# cataclysm-BOTTOM.net
KiCad netlist of a schematic drawn in EAGLE
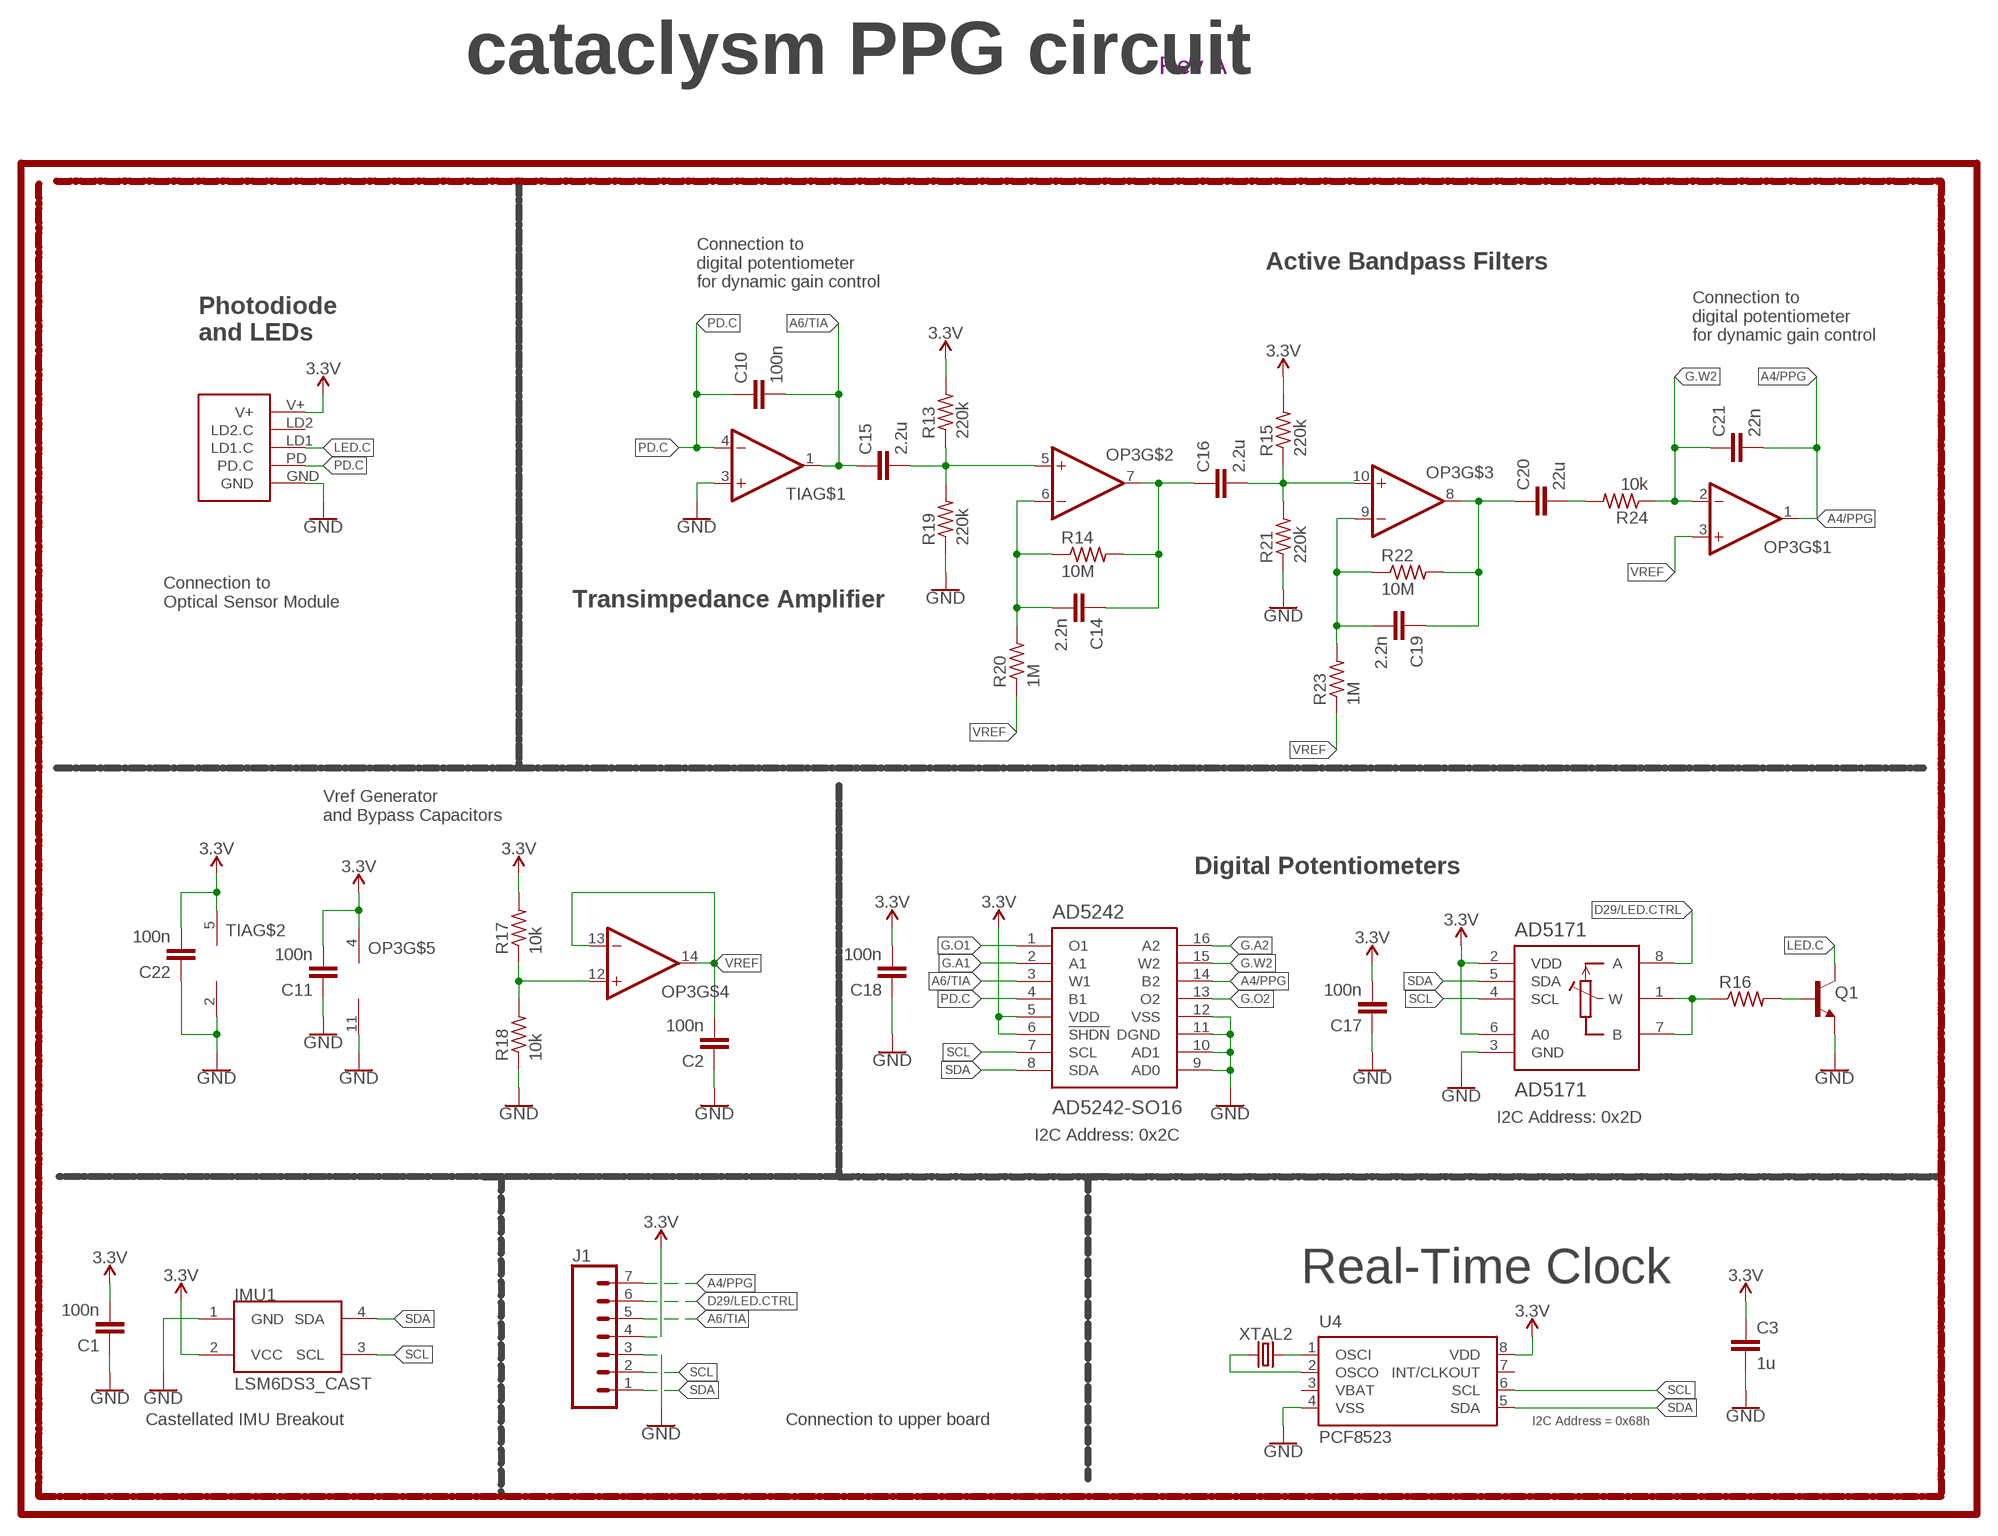
[diagram p0: schematic, sheet 1]

(export (version "E")
  (design (tool "Eeschema 10.0.6"))
  (components
    (comp (ref "AD5171")
      (value "AD5171")
      (footprint "eagle-import:SOT-23-8")
      (libsource (lib "eagle-import") (part "AD5171"))
    )
    (comp (ref "AD5242")
      (value "AD5242-SO16")
      (footprint "eagle-import:SO16")
      (libsource (lib "eagle-import") (part "AD5242-SO16"))
    )
    (comp (ref "C1")
      (value "100n")
      (footprint "eagle-import:C0603")
      (libsource (lib "eagle-import") (part "CAPACITOR0603"))
    )
    (comp (ref "C2")
      (value "100n")
      (footprint "eagle-import:C0603")
      (libsource (lib "eagle-import") (part "CAPACITOR0603"))
    )
    (comp (ref "C3")
      (value "1u")
      (footprint "eagle-import:C0603")
      (libsource (lib "eagle-import") (part "CAPACITOR0603"))
    )
    (comp (ref "C10")
      (value "100n")
      (footprint "eagle-import:C0603")
      (libsource (lib "eagle-import") (part "CAPACITOR0603"))
    )
    (comp (ref "C11")
      (value "100n")
      (footprint "eagle-import:C0603")
      (libsource (lib "eagle-import") (part "CAPACITOR0603"))
    )
    (comp (ref "C14")
      (value "2.2n")
      (footprint "eagle-import:C0603")
      (libsource (lib "eagle-import") (part "CAPACITOR0603"))
    )
    (comp (ref "C15")
      (value "2.2u")
      (footprint "eagle-import:C0603")
      (libsource (lib "eagle-import") (part "CAPACITOR0603"))
    )
    (comp (ref "C16")
      (value "2.2u")
      (footprint "eagle-import:C0603")
      (libsource (lib "eagle-import") (part "CAPACITOR0603"))
    )
    (comp (ref "C17")
      (value "100n")
      (footprint "eagle-import:C0603")
      (libsource (lib "eagle-import") (part "CAPACITOR0603"))
    )
    (comp (ref "C18")
      (value "100n")
      (footprint "eagle-import:C0603")
      (libsource (lib "eagle-import") (part "CAPACITOR0603"))
    )
    (comp (ref "C19")
      (value "2.2n")
      (footprint "eagle-import:C0603")
      (libsource (lib "eagle-import") (part "CAPACITOR0603"))
    )
    (comp (ref "C20")
      (value "22u")
      (footprint "eagle-import:C0603")
      (libsource (lib "eagle-import") (part "CAPACITOR0603"))
    )
    (comp (ref "C21")
      (value "22n")
      (footprint "eagle-import:C0603")
      (libsource (lib "eagle-import") (part "CAPACITOR0603"))
    )
    (comp (ref "C22")
      (value "100n")
      (footprint "eagle-import:C0603")
      (libsource (lib "eagle-import") (part "CAPACITOR0603"))
    )
    (comp (ref "IMU1")
      (value "LSM6DS3_CAST")
      (footprint "eagle-import:LSM6DS3_CAST")
      (libsource (lib "eagle-import") (part "LSM6DS3_CAST"))
    )
    (comp (ref "J1")
      (value "CONN_07-1.27MM")
      (footprint "eagle-import:1X07_1.27MM")
      (libsource (lib "eagle-import") (part "CONN_07-1.27MM"))
    )
    (comp (ref "LOGO1")
      (value "REVISION.A")
      (footprint "eagle-import:REV.A")
      (libsource (lib "eagle-import") (part "REVISION.A"))
    )
    (comp (ref "OP3")
      (value "OP-QUAD-SO14")
      (footprint "eagle-import:SO14")
      (libsource (lib "eagle-import") (part "OP-QUAD-SO14"))
    )
    (comp (ref "Q1")
      (value "NPN-GENERIC")
      (footprint "eagle-import:SOT23-3")
      (libsource (lib "eagle-import") (part "NPN-GENERIC"))
    )
    (comp (ref "R13")
      (value "220k")
      (footprint "eagle-import:R0603")
      (libsource (lib "eagle-import") (part "RESISTOR0603"))
    )
    (comp (ref "R14")
      (value "10M")
      (footprint "eagle-import:R0603")
      (libsource (lib "eagle-import") (part "RESISTOR0603"))
    )
    (comp (ref "R15")
      (value "220k")
      (footprint "eagle-import:R0603")
      (libsource (lib "eagle-import") (part "RESISTOR0603"))
    )
    (comp (ref "R16")
      (value "RESISTOR0603")
      (footprint "eagle-import:R0603")
      (libsource (lib "eagle-import") (part "RESISTOR0603"))
    )
    (comp (ref "R17")
      (value "10k")
      (footprint "eagle-import:R0402")
      (libsource (lib "eagle-import") (part "RESISTOR0402"))
    )
    (comp (ref "R18")
      (value "10k")
      (footprint "eagle-import:R0402")
      (libsource (lib "eagle-import") (part "RESISTOR0402"))
    )
    (comp (ref "R19")
      (value "220k")
      (footprint "eagle-import:R0603")
      (libsource (lib "eagle-import") (part "RESISTOR0603"))
    )
    (comp (ref "R20")
      (value "1M")
      (footprint "eagle-import:R0603")
      (libsource (lib "eagle-import") (part "RESISTOR0603"))
    )
    (comp (ref "R21")
      (value "220k")
      (footprint "eagle-import:R0603")
      (libsource (lib "eagle-import") (part "RESISTOR0603"))
    )
    (comp (ref "R22")
      (value "10M")
      (footprint "eagle-import:R0603")
      (libsource (lib "eagle-import") (part "RESISTOR0603"))
    )
    (comp (ref "R23")
      (value "1M")
      (footprint "eagle-import:R0603")
      (libsource (lib "eagle-import") (part "RESISTOR0603"))
    )
    (comp (ref "R24")
      (value "10k")
      (footprint "eagle-import:R0603")
      (libsource (lib "eagle-import") (part "RESISTOR0603"))
    )
    (comp (ref "TIA")
      (value "OP-SINGLEOT")
      (footprint "eagle-import:SOT23-5")
      (libsource (lib "eagle-import") (part "OP-SINGLEOT"))
    )
    (comp (ref "U$3")
      (value "PPG.MODULE.2")
      (footprint "eagle-import:PPG.MODULE.2")
      (libsource (lib "eagle-import") (part "PPG.MODULE.2"))
    )
    (comp (ref "U4")
      (value "PCF8523")
      (footprint "eagle-import:SO8")
      (libsource (lib "eagle-import") (part "PCF8523"))
    )
    (comp (ref "XTAL2")
      (value "32.7680kHz")
      (footprint "eagle-import:2-SMD.NOLEAD.2.0MMTO1.2MM")
      (fields (field (name "FREQ") "32.7680KHZ"))
      (libsource (lib "eagle-import") (part "CRYSTALECS-.327-12.5-12-C-TR"))
    )
  )
  (nets
    (net (code "1") (name "/VBAT") (class "Default")
      (node (ref "U4") (pin "3") (pinfunction "VBAT_3") (pintype "power_in"))
    )
    (net (code "2") (name "3.3V") (class "Default")
      (node (ref "AD5171") (pin "2") (pinfunction "VDD_2") (pintype "bidirectional"))
      (node (ref "AD5171") (pin "6") (pinfunction "A0_6") (pintype "bidirectional"))
      (node (ref "AD5242") (pin "5") (pinfunction "VDD_5") (pintype "bidirectional"))
      (node (ref "AD5242") (pin "6") (pinfunction "~{SHDN}_6") (pintype "bidirectional"))
      (node (ref "C1") (pin "2") (pinfunction "2_2") (pintype "passive"))
      (node (ref "C11") (pin "2") (pinfunction "2_2") (pintype "passive"))
      (node (ref "C17") (pin "2") (pinfunction "2_2") (pintype "passive"))
      (node (ref "C18") (pin "2") (pinfunction "2_2") (pintype "passive"))
      (node (ref "C22") (pin "2") (pinfunction "2_2") (pintype "passive"))
      (node (ref "C3") (pin "1") (pinfunction "1_1") (pintype "passive"))
      (node (ref "IMU1") (pin "2") (pinfunction "VCC_2") (pintype "bidirectional"))
      (node (ref "J1") (pin "4") (pinfunction "4_4") (pintype "passive"))
      (node (ref "OP3") (pin "4") (pinfunction "V+_4") (pintype "power_in"))
      (node (ref "R13") (pin "2") (pinfunction "2_2") (pintype "passive"))
      (node (ref "R15") (pin "2") (pinfunction "2_2") (pintype "passive"))
      (node (ref "R17") (pin "2") (pinfunction "2_2") (pintype "passive"))
      (node (ref "TIA") (pin "5") (pinfunction "V+_5") (pintype "power_in"))
      (node (ref "U$3") (pin "V+") (pinfunction "V+_V+") (pintype "bidirectional"))
      (node (ref "U4") (pin "8") (pinfunction "VDD_8") (pintype "power_in"))
    )
    (net (code "3") (name "A4{slash}PPG") (class "Default")
      (node (ref "AD5242") (pin "14") (pinfunction "B2_14") (pintype "bidirectional"))
      (node (ref "C21") (pin "2") (pinfunction "2_2") (pintype "passive"))
      (node (ref "J1") (pin "7") (pinfunction "7_7") (pintype "passive"))
      (node (ref "OP3") (pin "1") (pinfunction "OUT_1") (pintype "output"))
    )
    (net (code "4") (name "A6{slash}TIA") (class "Default")
      (node (ref "AD5242") (pin "3") (pinfunction "W1_3") (pintype "bidirectional"))
      (node (ref "C10") (pin "2") (pinfunction "2_2") (pintype "passive"))
      (node (ref "C15") (pin "1") (pinfunction "1_1") (pintype "passive"))
      (node (ref "J1") (pin "5") (pinfunction "5_5") (pintype "passive"))
      (node (ref "TIA") (pin "1") (pinfunction "OUT_1") (pintype "output"))
    )
    (net (code "5") (name "D29{slash}LED.CTRL") (class "Default")
      (node (ref "AD5171") (pin "8") (pinfunction "A_8") (pintype "bidirectional"))
      (node (ref "J1") (pin "6") (pinfunction "6_6") (pintype "passive"))
    )
    (net (code "6") (name "G.A1") (class "Default")
      (node (ref "AD5242") (pin "2") (pinfunction "A1_2") (pintype "bidirectional"))
    )
    (net (code "7") (name "G.A2") (class "Default")
      (node (ref "AD5242") (pin "16") (pinfunction "A2_16") (pintype "bidirectional"))
    )
    (net (code "8") (name "G.O1") (class "Default")
      (node (ref "AD5242") (pin "1") (pinfunction "O1_1") (pintype "bidirectional"))
    )
    (net (code "9") (name "G.O2") (class "Default")
      (node (ref "AD5242") (pin "13") (pinfunction "O2_13") (pintype "bidirectional"))
    )
    (net (code "10") (name "G.W2") (class "Default")
      (node (ref "AD5242") (pin "15") (pinfunction "W2_15") (pintype "bidirectional"))
      (node (ref "C21") (pin "1") (pinfunction "1_1") (pintype "passive"))
      (node (ref "OP3") (pin "2") (pinfunction "-IN_2") (pintype "input"))
      (node (ref "R24") (pin "1") (pinfunction "1_1") (pintype "passive"))
    )
    (net (code "11") (name "GND") (class "Default")
      (node (ref "AD5171") (pin "3") (pinfunction "GND_3") (pintype "bidirectional"))
      (node (ref "AD5242") (pin "10") (pinfunction "AD1_10") (pintype "bidirectional"))
      (node (ref "AD5242") (pin "11") (pinfunction "DGND_11") (pintype "bidirectional"))
      (node (ref "AD5242") (pin "12") (pinfunction "VSS_12") (pintype "bidirectional"))
      (node (ref "AD5242") (pin "9") (pinfunction "AD0_9") (pintype "bidirectional"))
      (node (ref "C1") (pin "1") (pinfunction "1_1") (pintype "passive"))
      (node (ref "C11") (pin "1") (pinfunction "1_1") (pintype "passive"))
      (node (ref "C17") (pin "1") (pinfunction "1_1") (pintype "passive"))
      (node (ref "C18") (pin "1") (pinfunction "1_1") (pintype "passive"))
      (node (ref "C2") (pin "1") (pinfunction "1_1") (pintype "passive"))
      (node (ref "C22") (pin "1") (pinfunction "1_1") (pintype "passive"))
      (node (ref "C3") (pin "2") (pinfunction "2_2") (pintype "passive"))
      (node (ref "IMU1") (pin "1") (pinfunction "GND_1") (pintype "bidirectional"))
      (node (ref "J1") (pin "3") (pinfunction "3_3") (pintype "passive"))
      (node (ref "OP3") (pin "11") (pinfunction "V-_11") (pintype "power_in"))
      (node (ref "Q1") (pin "2") (pinfunction "E_2") (pintype "passive"))
      (node (ref "R18") (pin "1") (pinfunction "1_1") (pintype "passive"))
      (node (ref "R19") (pin "1") (pinfunction "1_1") (pintype "passive"))
      (node (ref "R21") (pin "1") (pinfunction "1_1") (pintype "passive"))
      (node (ref "TIA") (pin "2") (pinfunction "V-_2") (pintype "power_in"))
      (node (ref "TIA") (pin "3") (pinfunction "+IN_3") (pintype "input"))
      (node (ref "U$3") (pin "GND") (pinfunction "GND_GND") (pintype "bidirectional"))
      (node (ref "U4") (pin "4") (pinfunction "VSS_4") (pintype "power_in"))
    )
    (net (code "12") (name "LED.C") (class "Default")
      (node (ref "Q1") (pin "3") (pinfunction "C_3") (pintype "passive"))
      (node (ref "U$3") (pin "LD1") (pinfunction "LD1.C_LD1") (pintype "bidirectional"))
    )
    (net (code "13") (name "Net-(AD5171-B)") (class "Default")
      (node (ref "AD5171") (pin "1") (pinfunction "W_1") (pintype "bidirectional"))
      (node (ref "AD5171") (pin "7") (pinfunction "B_7") (pintype "bidirectional"))
      (node (ref "R16") (pin "1") (pinfunction "1_1") (pintype "passive"))
    )
    (net (code "14") (name "Net-(C20-Pad2)") (class "Default")
      (node (ref "C20") (pin "2") (pinfunction "2_2") (pintype "passive"))
      (node (ref "R24") (pin "2") (pinfunction "2_2") (pintype "passive"))
    )
    (net (code "15") (name "Net-(OP3B-+IN)") (class "Default")
      (node (ref "C15") (pin "2") (pinfunction "2_2") (pintype "passive"))
      (node (ref "OP3") (pin "5") (pinfunction "+IN_5") (pintype "input"))
      (node (ref "R13") (pin "1") (pinfunction "1_1") (pintype "passive"))
      (node (ref "R19") (pin "2") (pinfunction "2_2") (pintype "passive"))
    )
    (net (code "16") (name "Net-(OP3B--IN)") (class "Default")
      (node (ref "C14") (pin "2") (pinfunction "2_2") (pintype "passive"))
      (node (ref "OP3") (pin "6") (pinfunction "-IN_6") (pintype "input"))
      (node (ref "R14") (pin "1") (pinfunction "1_1") (pintype "passive"))
      (node (ref "R20") (pin "2") (pinfunction "2_2") (pintype "passive"))
    )
    (net (code "17") (name "Net-(OP3B-OUT)") (class "Default")
      (node (ref "C14") (pin "1") (pinfunction "1_1") (pintype "passive"))
      (node (ref "C16") (pin "1") (pinfunction "1_1") (pintype "passive"))
      (node (ref "OP3") (pin "7") (pinfunction "OUT_7") (pintype "output"))
      (node (ref "R14") (pin "2") (pinfunction "2_2") (pintype "passive"))
    )
    (net (code "18") (name "Net-(OP3C-+IN)") (class "Default")
      (node (ref "C16") (pin "2") (pinfunction "2_2") (pintype "passive"))
      (node (ref "OP3") (pin "10") (pinfunction "+IN_10") (pintype "input"))
      (node (ref "R15") (pin "1") (pinfunction "1_1") (pintype "passive"))
      (node (ref "R21") (pin "2") (pinfunction "2_2") (pintype "passive"))
    )
    (net (code "19") (name "Net-(OP3C--IN)") (class "Default")
      (node (ref "C19") (pin "2") (pinfunction "2_2") (pintype "passive"))
      (node (ref "OP3") (pin "9") (pinfunction "-IN_9") (pintype "input"))
      (node (ref "R22") (pin "1") (pinfunction "1_1") (pintype "passive"))
      (node (ref "R23") (pin "2") (pinfunction "2_2") (pintype "passive"))
    )
    (net (code "20") (name "Net-(OP3C-OUT)") (class "Default")
      (node (ref "C19") (pin "1") (pinfunction "1_1") (pintype "passive"))
      (node (ref "C20") (pin "1") (pinfunction "1_1") (pintype "passive"))
      (node (ref "OP3") (pin "8") (pinfunction "OUT_8") (pintype "output"))
      (node (ref "R22") (pin "2") (pinfunction "2_2") (pintype "passive"))
    )
    (net (code "21") (name "Net-(OP3D-+IN)") (class "Default")
      (node (ref "OP3") (pin "12") (pinfunction "+IN_12") (pintype "input"))
      (node (ref "R17") (pin "1") (pinfunction "1_1") (pintype "passive"))
      (node (ref "R18") (pin "2") (pinfunction "2_2") (pintype "passive"))
    )
    (net (code "22") (name "Net-(Q1-B)") (class "Default")
      (node (ref "Q1") (pin "1") (pinfunction "B_1") (pintype "passive"))
      (node (ref "R16") (pin "2") (pinfunction "2_2") (pintype "passive"))
    )
    (net (code "23") (name "Net-(U4-OSCI)") (class "Default")
      (node (ref "U4") (pin "1") (pinfunction "OSCI_1") (pintype "bidirectional"))
      (node (ref "XTAL2") (pin "P$2") (pinfunction "2_P$2") (pintype "passive"))
    )
    (net (code "24") (name "Net-(U4-OSCO)") (class "Default")
      (node (ref "U4") (pin "2") (pinfunction "OSCO_2") (pintype "bidirectional"))
      (node (ref "XTAL2") (pin "P$1") (pinfunction "1_P$1") (pintype "passive"))
    )
    (net (code "25") (name "PD.C") (class "Default")
      (node (ref "AD5242") (pin "4") (pinfunction "B1_4") (pintype "bidirectional"))
      (node (ref "C10") (pin "1") (pinfunction "1_1") (pintype "passive"))
      (node (ref "TIA") (pin "4") (pinfunction "-IN_4") (pintype "input"))
      (node (ref "U$3") (pin "PD") (pinfunction "PD.C_PD") (pintype "bidirectional"))
    )
    (net (code "26") (name "SCL") (class "Default")
      (node (ref "AD5171") (pin "4") (pinfunction "SCL_4") (pintype "bidirectional"))
      (node (ref "AD5242") (pin "7") (pinfunction "SCL_7") (pintype "bidirectional"))
      (node (ref "IMU1") (pin "3") (pinfunction "SCL_3") (pintype "bidirectional"))
      (node (ref "J1") (pin "2") (pinfunction "2_2") (pintype "passive"))
      (node (ref "U4") (pin "6") (pinfunction "SCL_6") (pintype "bidirectional"))
    )
    (net (code "27") (name "SDA") (class "Default")
      (node (ref "AD5171") (pin "5") (pinfunction "SDA_5") (pintype "bidirectional"))
      (node (ref "AD5242") (pin "8") (pinfunction "SDA_8") (pintype "bidirectional"))
      (node (ref "IMU1") (pin "4") (pinfunction "SDA_4") (pintype "bidirectional"))
      (node (ref "J1") (pin "1") (pinfunction "1_1") (pintype "passive"))
      (node (ref "U4") (pin "5") (pinfunction "SDA_5") (pintype "bidirectional"))
    )
    (net (code "28") (name "VREF") (class "Default")
      (node (ref "C2") (pin "2") (pinfunction "2_2") (pintype "passive"))
      (node (ref "OP3") (pin "13") (pinfunction "-IN_13") (pintype "input"))
      (node (ref "OP3") (pin "14") (pinfunction "OUT_14") (pintype "output"))
      (node (ref "OP3") (pin "3") (pinfunction "+IN_3") (pintype "input"))
      (node (ref "R20") (pin "1") (pinfunction "1_1") (pintype "passive"))
      (node (ref "R23") (pin "1") (pinfunction "1_1") (pintype "passive"))
    )
    (net (code "29") (name "unconnected-(U$3-LD2.C-PadLD2)") (class "Default")
      (node (ref "U$3") (pin "LD2") (pinfunction "LD2.C_LD2") (pintype "bidirectional"))
    )
    (net (code "30") (name "unconnected-(U4-INT{slash}CLKOUT-Pad7)") (class "Default")
      (node (ref "U4") (pin "7") (pinfunction "INT/CLKOUT_7") (pintype "bidirectional"))
    )
  )
)
